# Pulsioximetro.net
KiCad netlist of a schematic drawn in EAGLE
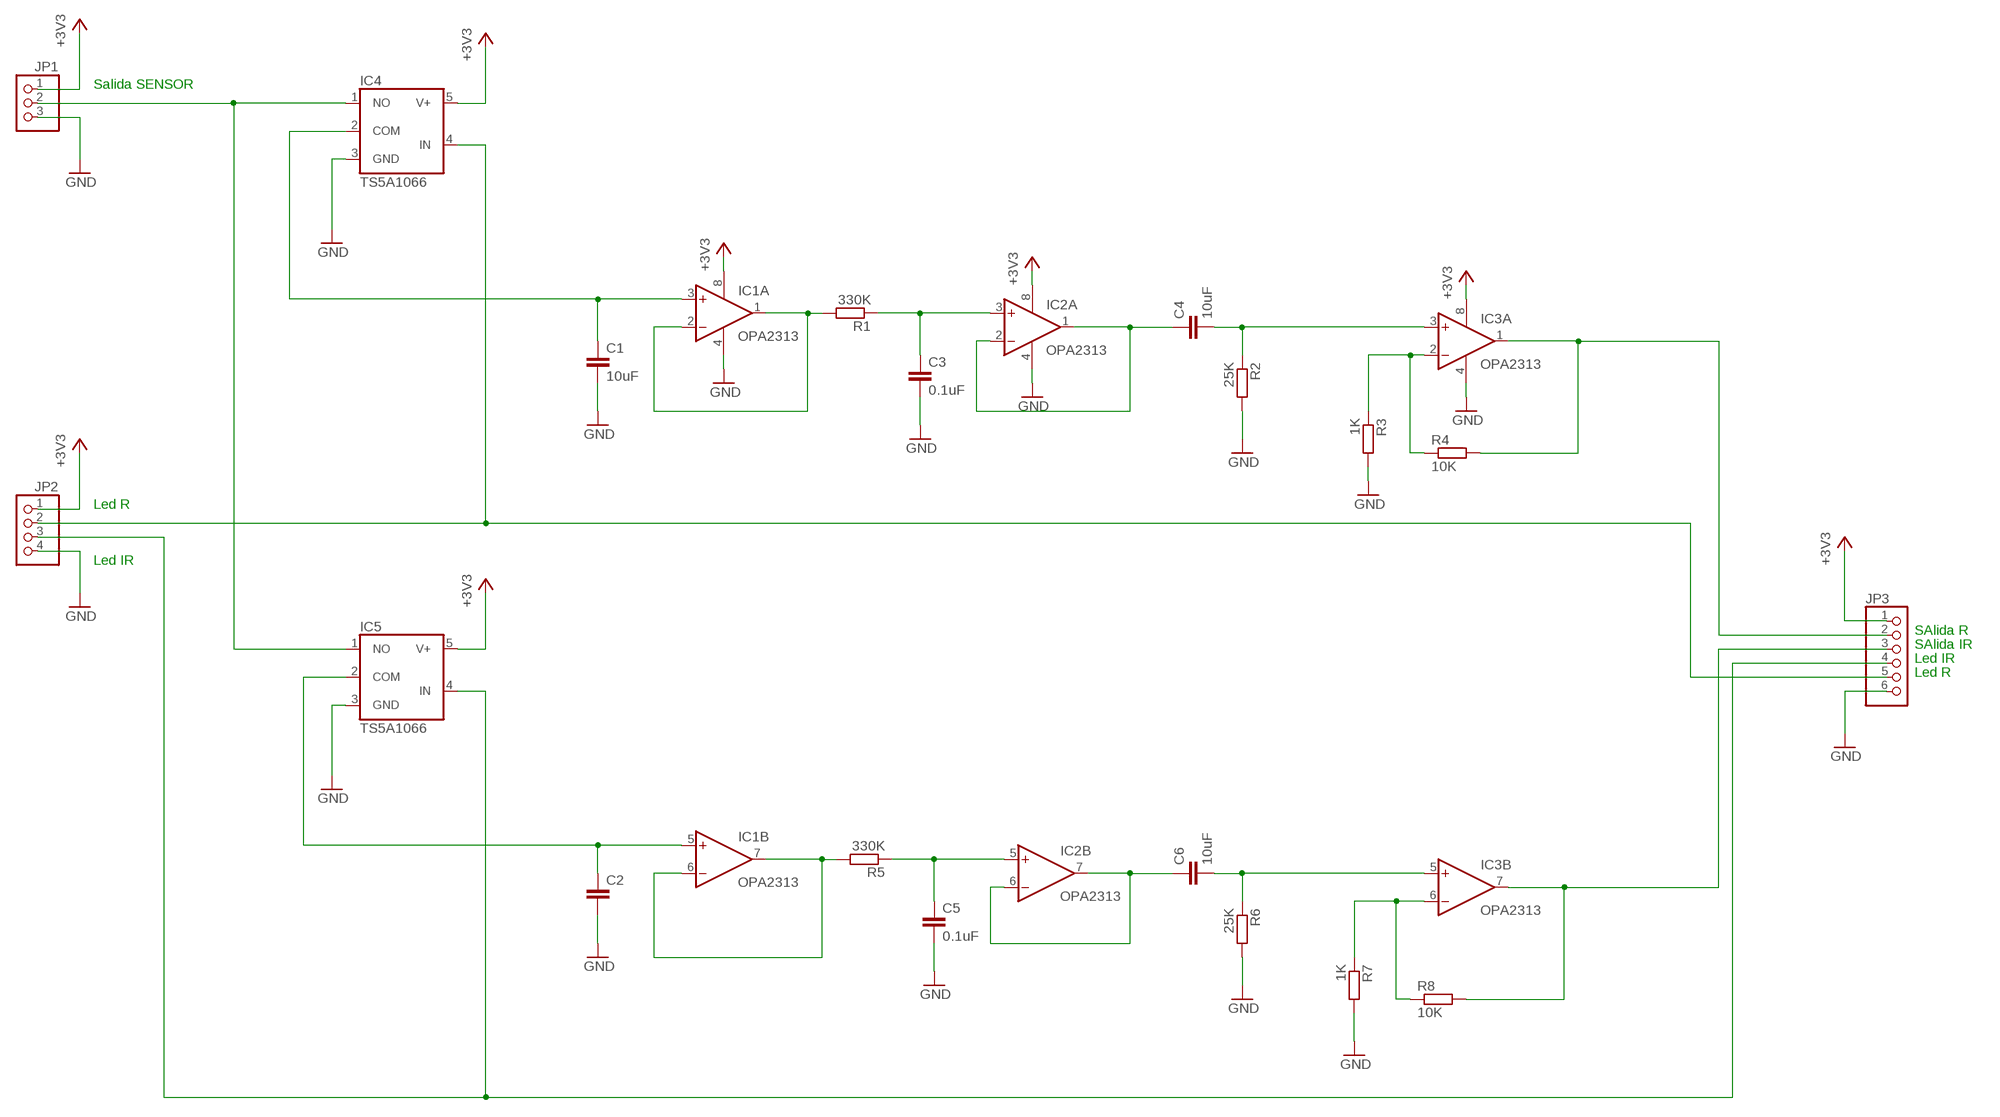
[diagram p0: schematic, sheet 1]

(export (version "E")
  (design (tool "Eeschema 10.0.6"))
  (components
    (comp (ref "C1")
      (value "10uF")
      (footprint "eagle-import:C050-024X044")
      (libsource (lib "eagle-import") (part "C-EU050-024X044"))
    )
    (comp (ref "C2")
      (value "C-EU050-024X044")
      (footprint "eagle-import:C050-024X044")
      (libsource (lib "eagle-import") (part "C-EU050-024X044"))
    )
    (comp (ref "C3")
      (value "0.1uF")
      (footprint "eagle-import:C050-024X044")
      (libsource (lib "eagle-import") (part "C-EU050-024X044"))
    )
    (comp (ref "C4")
      (value "10uF")
      (footprint "eagle-import:C050-024X044")
      (libsource (lib "eagle-import") (part "C-EU050-024X044"))
    )
    (comp (ref "C5")
      (value "0.1uF")
      (footprint "eagle-import:C050-024X044")
      (libsource (lib "eagle-import") (part "C-EU050-024X044"))
    )
    (comp (ref "C6")
      (value "10uF")
      (footprint "eagle-import:C050-024X044")
      (libsource (lib "eagle-import") (part "C-EU050-024X044"))
    )
    (comp (ref "IC1")
      (value "OPA2313")
      (footprint "eagle-import:SO08")
      (libsource (lib "eagle-import") (part "TL082D"))
    )
    (comp (ref "IC2")
      (value "OPA2313")
      (footprint "eagle-import:SO08")
      (libsource (lib "eagle-import") (part "TL082D"))
    )
    (comp (ref "IC3")
      (value "OPA2313")
      (footprint "eagle-import:SO08")
      (libsource (lib "eagle-import") (part "TL082D"))
    )
    (comp (ref "IC4")
      (value "TS5A1066")
      (footprint "eagle-import:SOT25")
      (libsource (lib "eagle-import") (part "TS520550"))
    )
    (comp (ref "IC5")
      (value "TS5A1066")
      (footprint "eagle-import:SOT25")
      (libsource (lib "eagle-import") (part "TS520550"))
    )
    (comp (ref "JP1")
      (value "PINHD-1X3")
      (footprint "eagle-import:1X03")
      (libsource (lib "eagle-import") (part "PINHD-1X3"))
    )
    (comp (ref "JP2")
      (value "PINHD-1X4")
      (footprint "eagle-import:1X04")
      (libsource (lib "eagle-import") (part "PINHD-1X4"))
    )
    (comp (ref "JP3")
      (value "PINHD-1X6")
      (footprint "eagle-import:1X06")
      (libsource (lib "eagle-import") (part "PINHD-1X6"))
    )
    (comp (ref "R1")
      (value "330K")
      (footprint "eagle-import:0207_10")
      (libsource (lib "eagle-import") (part "R-EU_0207/10"))
    )
    (comp (ref "R2")
      (value "25K")
      (footprint "eagle-import:0207_10")
      (libsource (lib "eagle-import") (part "R-EU_0207/10"))
    )
    (comp (ref "R3")
      (value "1K")
      (footprint "eagle-import:0207_10")
      (libsource (lib "eagle-import") (part "R-EU_0207/10"))
    )
    (comp (ref "R4")
      (value "10K")
      (footprint "eagle-import:0207_10")
      (libsource (lib "eagle-import") (part "R-EU_0207/10"))
    )
    (comp (ref "R5")
      (value "330K")
      (footprint "eagle-import:0207_10")
      (libsource (lib "eagle-import") (part "R-EU_0207/10"))
    )
    (comp (ref "R6")
      (value "25K")
      (footprint "eagle-import:0207_10")
      (libsource (lib "eagle-import") (part "R-EU_0207/10"))
    )
    (comp (ref "R7")
      (value "1K")
      (footprint "eagle-import:0207_10")
      (libsource (lib "eagle-import") (part "R-EU_0207/10"))
    )
    (comp (ref "R8")
      (value "10K")
      (footprint "eagle-import:0207_10")
      (libsource (lib "eagle-import") (part "R-EU_0207/10"))
    )
  )
  (nets
    (net (code "1") (name "+3V3") (class "Default")
      (node (ref "IC1") (pin "8") (pinfunction "V+_8") (pintype "power_in"))
      (node (ref "IC2") (pin "8") (pinfunction "V+_8") (pintype "power_in"))
      (node (ref "IC3") (pin "8") (pinfunction "V+_8") (pintype "power_in"))
      (node (ref "IC4") (pin "5") (pinfunction "V+_5") (pintype "passive"))
      (node (ref "IC5") (pin "5") (pinfunction "V+_5") (pintype "passive"))
      (node (ref "JP1") (pin "1") (pinfunction "1_1") (pintype "passive"))
      (node (ref "JP2") (pin "1") (pinfunction "1_1") (pintype "passive"))
      (node (ref "JP3") (pin "1") (pinfunction "1_1") (pintype "passive"))
    )
    (net (code "2") (name "GND") (class "Default")
      (node (ref "C1") (pin "2") (pinfunction "2_2") (pintype "passive"))
      (node (ref "C2") (pin "2") (pinfunction "2_2") (pintype "passive"))
      (node (ref "C3") (pin "2") (pinfunction "2_2") (pintype "passive"))
      (node (ref "C5") (pin "2") (pinfunction "2_2") (pintype "passive"))
      (node (ref "IC1") (pin "4") (pinfunction "V-_4") (pintype "power_in"))
      (node (ref "IC2") (pin "4") (pinfunction "V-_4") (pintype "power_in"))
      (node (ref "IC3") (pin "4") (pinfunction "V-_4") (pintype "power_in"))
      (node (ref "IC4") (pin "3") (pinfunction "GND_3") (pintype "input"))
      (node (ref "IC5") (pin "3") (pinfunction "GND_3") (pintype "input"))
      (node (ref "JP1") (pin "3") (pinfunction "3_3") (pintype "passive"))
      (node (ref "JP2") (pin "4") (pinfunction "4_4") (pintype "passive"))
      (node (ref "JP3") (pin "6") (pinfunction "6_6") (pintype "passive"))
      (node (ref "R2") (pin "2") (pinfunction "2_2") (pintype "passive"))
      (node (ref "R3") (pin "2") (pinfunction "2_2") (pintype "passive"))
      (node (ref "R6") (pin "2") (pinfunction "2_2") (pintype "passive"))
      (node (ref "R7") (pin "2") (pinfunction "2_2") (pintype "passive"))
    )
    (net (code "3") (name "Net-(IC1A-+IN)") (class "Default")
      (node (ref "C1") (pin "1") (pinfunction "1_1") (pintype "passive"))
      (node (ref "IC1") (pin "3") (pinfunction "+IN_3") (pintype "input"))
      (node (ref "IC4") (pin "2") (pinfunction "COM_2") (pintype "passive"))
    )
    (net (code "4") (name "Net-(IC1A--IN)") (class "Default")
      (node (ref "IC1") (pin "1") (pinfunction "OUT_1") (pintype "output"))
      (node (ref "IC1") (pin "2") (pinfunction "-IN_2") (pintype "input"))
      (node (ref "R1") (pin "2") (pinfunction "2_2") (pintype "passive"))
    )
    (net (code "5") (name "Net-(IC1B-+IN)") (class "Default")
      (node (ref "C2") (pin "1") (pinfunction "1_1") (pintype "passive"))
      (node (ref "IC1") (pin "5") (pinfunction "+IN_5") (pintype "input"))
      (node (ref "IC5") (pin "2") (pinfunction "COM_2") (pintype "passive"))
    )
    (net (code "6") (name "Net-(IC1B--IN)") (class "Default")
      (node (ref "IC1") (pin "6") (pinfunction "-IN_6") (pintype "input"))
      (node (ref "IC1") (pin "7") (pinfunction "OUT_7") (pintype "output"))
      (node (ref "R5") (pin "2") (pinfunction "2_2") (pintype "passive"))
    )
    (net (code "7") (name "Net-(IC2A-+IN)") (class "Default")
      (node (ref "C3") (pin "1") (pinfunction "1_1") (pintype "passive"))
      (node (ref "IC2") (pin "3") (pinfunction "+IN_3") (pintype "input"))
      (node (ref "R1") (pin "1") (pinfunction "1_1") (pintype "passive"))
    )
    (net (code "8") (name "Net-(IC2A--IN)") (class "Default")
      (node (ref "C4") (pin "1") (pinfunction "1_1") (pintype "passive"))
      (node (ref "IC2") (pin "1") (pinfunction "OUT_1") (pintype "output"))
      (node (ref "IC2") (pin "2") (pinfunction "-IN_2") (pintype "input"))
    )
    (net (code "9") (name "Net-(IC2B-+IN)") (class "Default")
      (node (ref "C5") (pin "1") (pinfunction "1_1") (pintype "passive"))
      (node (ref "IC2") (pin "5") (pinfunction "+IN_5") (pintype "input"))
      (node (ref "R5") (pin "1") (pinfunction "1_1") (pintype "passive"))
    )
    (net (code "10") (name "Net-(IC2B--IN)") (class "Default")
      (node (ref "C6") (pin "1") (pinfunction "1_1") (pintype "passive"))
      (node (ref "IC2") (pin "6") (pinfunction "-IN_6") (pintype "input"))
      (node (ref "IC2") (pin "7") (pinfunction "OUT_7") (pintype "output"))
    )
    (net (code "11") (name "Net-(IC3A-+IN)") (class "Default")
      (node (ref "C4") (pin "2") (pinfunction "2_2") (pintype "passive"))
      (node (ref "IC3") (pin "3") (pinfunction "+IN_3") (pintype "input"))
      (node (ref "R2") (pin "1") (pinfunction "1_1") (pintype "passive"))
    )
    (net (code "12") (name "Net-(IC3A--IN)") (class "Default")
      (node (ref "IC3") (pin "2") (pinfunction "-IN_2") (pintype "input"))
      (node (ref "R3") (pin "1") (pinfunction "1_1") (pintype "passive"))
      (node (ref "R4") (pin "1") (pinfunction "1_1") (pintype "passive"))
    )
    (net (code "13") (name "Net-(IC3A-OUT)") (class "Default")
      (node (ref "IC3") (pin "1") (pinfunction "OUT_1") (pintype "output"))
      (node (ref "JP3") (pin "2") (pinfunction "2_2") (pintype "passive"))
      (node (ref "R4") (pin "2") (pinfunction "2_2") (pintype "passive"))
    )
    (net (code "14") (name "Net-(IC3B-+IN)") (class "Default")
      (node (ref "C6") (pin "2") (pinfunction "2_2") (pintype "passive"))
      (node (ref "IC3") (pin "5") (pinfunction "+IN_5") (pintype "input"))
      (node (ref "R6") (pin "1") (pinfunction "1_1") (pintype "passive"))
    )
    (net (code "15") (name "Net-(IC3B--IN)") (class "Default")
      (node (ref "IC3") (pin "6") (pinfunction "-IN_6") (pintype "input"))
      (node (ref "R7") (pin "1") (pinfunction "1_1") (pintype "passive"))
      (node (ref "R8") (pin "1") (pinfunction "1_1") (pintype "passive"))
    )
    (net (code "16") (name "Net-(IC3B-OUT)") (class "Default")
      (node (ref "IC3") (pin "7") (pinfunction "OUT_7") (pintype "output"))
      (node (ref "JP3") (pin "3") (pinfunction "3_3") (pintype "passive"))
      (node (ref "R8") (pin "2") (pinfunction "2_2") (pintype "passive"))
    )
    (net (code "17") (name "Net-(IC4-IN)") (class "Default")
      (node (ref "IC4") (pin "4") (pinfunction "IN_4") (pintype "input"))
      (node (ref "JP2") (pin "2") (pinfunction "2_2") (pintype "passive"))
      (node (ref "JP3") (pin "5") (pinfunction "5_5") (pintype "passive"))
    )
    (net (code "18") (name "Net-(IC4-NO)") (class "Default")
      (node (ref "IC4") (pin "1") (pinfunction "NO_1") (pintype "input"))
      (node (ref "IC5") (pin "1") (pinfunction "NO_1") (pintype "input"))
      (node (ref "JP1") (pin "2") (pinfunction "2_2") (pintype "passive"))
    )
    (net (code "19") (name "Net-(IC5-IN)") (class "Default")
      (node (ref "IC5") (pin "4") (pinfunction "IN_4") (pintype "input"))
      (node (ref "JP2") (pin "3") (pinfunction "3_3") (pintype "passive"))
      (node (ref "JP3") (pin "4") (pinfunction "4_4") (pintype "passive"))
    )
  )
)
